# NRF52833.net
KiCad netlist of a schematic drawn in Altium Designer
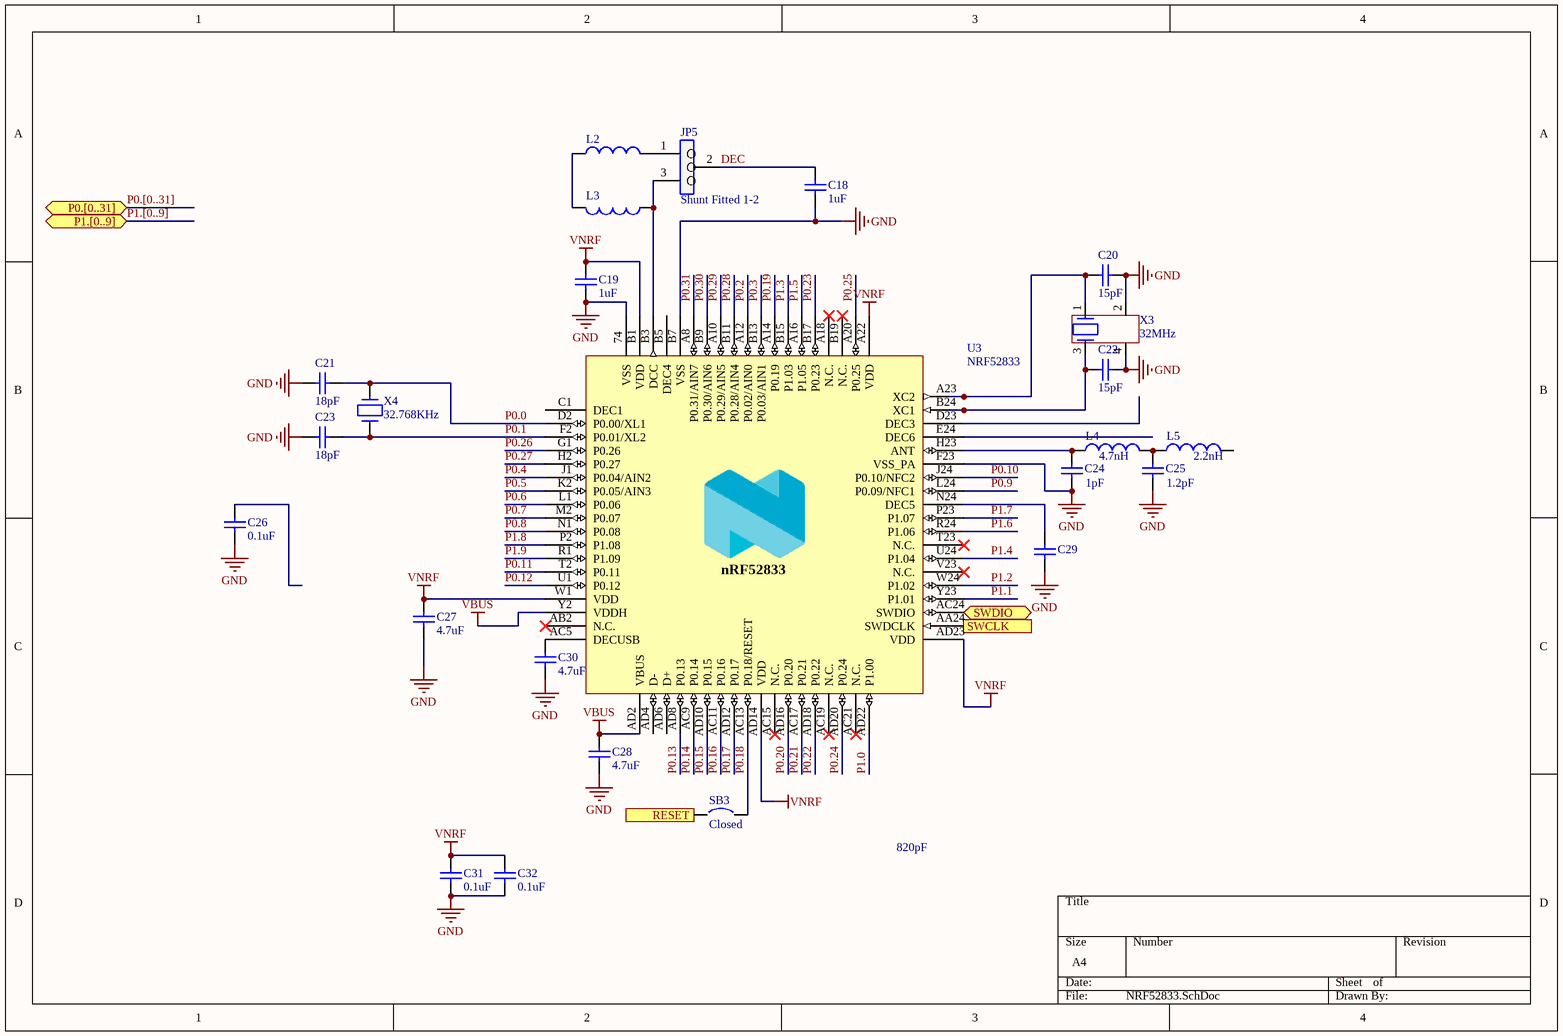
[diagram p0: NRF52833.SchDoc]

(export (version "E")
  (design (tool "Eeschema 10.0.6"))
  (components
    (comp (ref "C18")
      (value "1uF")
      (footprint "C0603[1608X92]")
      (description "1uF 6.3V 10% 0603 (1608 Metric)")
      (fields (field (name "PARTNUMBER") "GRM188R60J105KA01D") (field (name "MANUFACTURER") "Murata"))
      (libsource (lib "Capacitors") (part "CAP_1uF_6.3V_0603_10%"))
    )
    (comp (ref "C19")
      (value "1uF")
      (footprint "C0603[1608X92]")
      (description "1uF 6.3V 10% 0603 (1608 Metric)")
      (fields (field (name "PARTNUMBER") "GRM188R60J105KA01D") (field (name "MANUFACTURER") "Murata"))
      (libsource (lib "Capacitors") (part "CAP_1uF_6.3V_0603_10%"))
    )
    (comp (ref "C20")
      (value "15pF")
      (footprint "C0603[1608X92]")
      (description "15pF 50V 1% 0603 (1608 Metric)")
      (fields (field (name "PARTNUMBER") "06035A150FAT2A") (field (name "MANUFACTURER") "AVX Corporation"))
      (libsource (lib "Capacitors") (part "CAP_15pF_50V_0603_1%"))
    )
    (comp (ref "C21")
      (value "18pF")
      (footprint "C0603[1608X92]")
      (description "18pF 50V 1% 0603 (1608 Metric)")
      (fields (field (name "PARTNUMBER") "06035A180FAT2A") (field (name "MANUFACTURER") "AVX Corporation"))
      (libsource (lib "Capacitors") (part "CAP_18pF_50V_0603_1%"))
    )
    (comp (ref "C22")
      (value "15pF")
      (footprint "C0603[1608X92]")
      (description "15pF 50V 1% 0603 (1608 Metric)")
      (fields (field (name "PARTNUMBER") "06035A150FAT2A") (field (name "MANUFACTURER") "AVX Corporation"))
      (libsource (lib "Capacitors") (part "CAP_15pF_50V_0603_1%"))
    )
    (comp (ref "C23")
      (value "18pF")
      (footprint "C0603[1608X92]")
      (description "18pF 50V 1% 0603 (1608 Metric)")
      (fields (field (name "PARTNUMBER") "06035A180FAT2A") (field (name "MANUFACTURER") "AVX Corporation"))
      (libsource (lib "Capacitors") (part "CAP_18pF_50V_0603_1%"))
    )
    (comp (ref "C24")
      (value "CAPACITOR 0603")
      (footprint "C0603[1608X92]")
      (description "Empty CAPACITOR 0603 (1608 Metric)")
      (libsource (lib "Capacitors") (part "CAP 0603"))
    )
    (comp (ref "C25")
      (value "CAPACITOR 0603")
      (footprint "C0603[1608X92]")
      (description "Empty CAPACITOR 0603 (1608 Metric)")
      (libsource (lib "Capacitors") (part "CAP 0603"))
    )
    (comp (ref "C26")
      (value "0.1uF")
      (footprint "C0603[1608X92]")
      (description "0.1uF 16V 10% 0603 (1608 Metric)")
      (fields (field (name "PARTNUMBER") "GCM188R71C104KA37D") (field (name "MANUFACTURER") "Murata"))
      (libsource (lib "Capacitors") (part "CAP_0.1uF_16V_0603_10%"))
    )
    (comp (ref "C27")
      (value "4.7uF")
      (footprint "C0603[1608X92]")
      (description "4.7uF 16V 10% 0603 (1608 Metric)")
      (fields (field (name "PARTNUMBER") "GRM188R61A475KE15D") (field (name "MANUFACTURER") "Murata"))
      (libsource (lib "Capacitors") (part "CAP_4.7uF_16V_0603_10%"))
    )
    (comp (ref "C28")
      (value "4.7uF")
      (footprint "C0603[1608X92]")
      (description "4.7uF 16V 10% 0603 (1608 Metric)")
      (fields (field (name "PARTNUMBER") "GRM188R61A475KE15D") (field (name "MANUFACTURER") "Murata"))
      (libsource (lib "Capacitors") (part "CAP_4.7uF_16V_0603_10%"))
    )
    (comp (ref "C29")
      (value "CAPACITOR 0603")
      (footprint "C0603[1608X92]")
      (description "Empty CAPACITOR 0603 (1608 Metric)")
      (libsource (lib "Capacitors") (part "CAP 0603"))
    )
    (comp (ref "C30")
      (value "4.7uF")
      (footprint "C0603[1608X92]")
      (description "4.7uF 16V 10% 0603 (1608 Metric)")
      (fields (field (name "PARTNUMBER") "GRM188R61A475KE15D") (field (name "MANUFACTURER") "Murata"))
      (libsource (lib "Capacitors") (part "CAP_4.7uF_16V_0603_10%"))
    )
    (comp (ref "C31")
      (value "0.1uF")
      (footprint "C0603[1608X92]")
      (description "0.1uF 16V 10% 0603 (1608 Metric)")
      (fields (field (name "PARTNUMBER") "GCM188R71C104KA37D") (field (name "MANUFACTURER") "Murata"))
      (libsource (lib "Capacitors") (part "CAP_0.1uF_16V_0603_10%"))
    )
    (comp (ref "C32")
      (value "0.1uF")
      (footprint "C0603[1608X92]")
      (description "0.1uF 16V 10% 0603 (1608 Metric)")
      (fields (field (name "PARTNUMBER") "GCM188R71C104KA37D") (field (name "MANUFACTURER") "Murata"))
      (libsource (lib "Capacitors") (part "CAP_0.1uF_16V_0603_10%"))
    )
    (comp (ref "JP5")
      (value "Shunt Fitted 1-2")
      (footprint "HDR1X3")
      (description "Header, 3x1, 2,54mm, VR, TH, Height 5.84mm/2.54mm - Shunt Fitted 1-2 by default")
      (fields
        (field (name "INTERNAL_PART_NUMBER") "MCD-00684")
        (field (name "MANUFACTURER_PART_NUMBER") "TSW-103-07-F-S")
        (field (name "PROVIDED_BY") "SUBCO")
      )
      (libsource (lib "Connectors") (part "Jumper_Header 3x1 Fitted 1-2"))
    )
    (comp (ref "L2")
      (value "INDUCTOR 0603")
      (footprint "IND0603")
      (description "Empty INDUCTOR 0603")
      (libsource (lib "Inductors") (part "IND 0603"))
    )
    (comp (ref "L3")
      (value "INDUCTOR 0603")
      (footprint "IND0603")
      (description "Empty INDUCTOR 0603")
      (libsource (lib "Inductors") (part "IND 0603"))
    )
    (comp (ref "L4")
      (value "INDUCTOR 0603")
      (footprint "IND0603")
      (description "Empty INDUCTOR 0603")
      (libsource (lib "Inductors") (part "IND 0603"))
    )
    (comp (ref "L5")
      (value "INDUCTOR 0603")
      (footprint "IND0603")
      (description "Empty INDUCTOR 0603")
      (libsource (lib "Inductors") (part "IND 0603"))
    )
    (comp (ref "SB3")
      (value "Closed")
      (footprint "SB_0603")
      (description "Circuit Breaker")
      (fields (field (name "PUBLISHER") "Altium Limited"))
      (libsource (lib "Inductors") (part "Circuit Breaker_close"))
    )
    (comp (ref "U3")
      (value "NRF52833")
      (footprint "AQFN-73")
      (description "Multi-protocol Bluetooth Low Energy, IEEE 802.15.4, ANT and 2.4GHz proprietary system-on-chip")
      (fields
        (field (name "PARTNUMBER") "nRF52833-QIAA")
        (field (name "MANUFACTURER") "Nordic Semiconductor")
      )
      (libsource (lib "ICs") (part "NRF52833"))
    )
    (comp (ref "X3")
      (value "32MHz")
      (footprint "4-SMD")
      (description "Crystal 32MHz, 6pF, +-10ppm, 60ohms max, SMD")
      (fields (field (name "PARTNUMBER") "NX2016SA-32MHZ-EXS00A-CS07977") (field (name "MANUFACTURER") "NDK"))
      (libsource (lib "Oscillators") (part "NX2016SA 32MHz"))
    )
    (comp (ref "X4")
      (value "32.768KHz")
      (footprint "2-SMD")
      (description "Crystal 32.768kHz, 6pF, +-20ppm, 50Kohms max, SMD")
      (fields
        (field (name "PARTNUMBER") "NX3215SA-32.768KHz-EXS00A-MU00525")
        (field (name "MANUFACTURER") "NDK")
      )
      (libsource (lib "Oscillators") (part "NX3215SA 32.768KHz"))
    )
  )
  (nets
    (net (code "1") (name "/DEC") (class "Default")
      (node (ref "C18") (pin "2") (pinfunction "2_2") (pintype "passive"))
      (node (ref "JP5") (pin "2") (pinfunction "2_2") (pintype "passive"))
    )
    (net (code "2") (name "/P0.0") (class "Default")
      (node (ref "C21") (pin "1") (pinfunction "1_1") (pintype "passive"))
      (node (ref "U3") (pin "D2") (pinfunction "P0.00/XL1_D2") (pintype "bidirectional"))
      (node (ref "X4") (pin "2") (pinfunction "X2_2") (pintype "passive"))
    )
    (net (code "3") (name "/P0.1") (class "Default")
      (node (ref "C23") (pin "1") (pinfunction "1_1") (pintype "passive"))
      (node (ref "U3") (pin "F2") (pinfunction "P0.01/XL2_F2") (pintype "bidirectional"))
      (node (ref "X4") (pin "1") (pinfunction "X1_1") (pintype "passive"))
    )
    (net (code "4") (name "/P0.2") (class "Default")
      (node (ref "U3") (pin "A12") (pinfunction "P0.02/AIN0_A12") (pintype "bidirectional"))
    )
    (net (code "5") (name "/P0.3") (class "Default")
      (node (ref "U3") (pin "B13") (pinfunction "P0.03/AIN1_B13") (pintype "bidirectional"))
    )
    (net (code "6") (name "/P0.4") (class "Default")
      (node (ref "U3") (pin "J1") (pinfunction "P0.04/AIN2_J1") (pintype "bidirectional"))
    )
    (net (code "7") (name "/P0.5") (class "Default")
      (node (ref "U3") (pin "K2") (pinfunction "P0.05/AIN3_K2") (pintype "bidirectional"))
    )
    (net (code "8") (name "/P0.6") (class "Default")
      (node (ref "U3") (pin "L1") (pinfunction "P0.06_L1") (pintype "bidirectional"))
    )
    (net (code "9") (name "/P0.7") (class "Default")
      (node (ref "U3") (pin "M2") (pinfunction "P0.07_M2") (pintype "bidirectional"))
    )
    (net (code "10") (name "/P0.8") (class "Default")
      (node (ref "U3") (pin "N1") (pinfunction "P0.08_N1") (pintype "bidirectional"))
    )
    (net (code "11") (name "/P0.9") (class "Default")
      (node (ref "U3") (pin "L24") (pinfunction "P0.09/NFC1_L24") (pintype "bidirectional"))
    )
    (net (code "12") (name "/P0.10") (class "Default")
      (node (ref "U3") (pin "J24") (pinfunction "P0.10/NFC2_J24") (pintype "bidirectional"))
    )
    (net (code "13") (name "/P0.11") (class "Default")
      (node (ref "U3") (pin "T2") (pinfunction "P0.11_T2") (pintype "bidirectional"))
    )
    (net (code "14") (name "/P0.12") (class "Default")
      (node (ref "U3") (pin "U1") (pinfunction "P0.12_U1") (pintype "bidirectional"))
    )
    (net (code "15") (name "/P0.13") (class "Default")
      (node (ref "U3") (pin "AD8") (pinfunction "P0.13_AD8") (pintype "bidirectional"))
    )
    (net (code "16") (name "/P0.14") (class "Default")
      (node (ref "U3") (pin "AC9") (pinfunction "P0.14_AC9") (pintype "bidirectional"))
    )
    (net (code "17") (name "/P0.15") (class "Default")
      (node (ref "U3") (pin "AD10") (pinfunction "P0.15_AD10") (pintype "bidirectional"))
    )
    (net (code "18") (name "/P0.16") (class "Default")
      (node (ref "U3") (pin "AC11") (pinfunction "P0.16_AC11") (pintype "bidirectional"))
    )
    (net (code "19") (name "/P0.17") (class "Default")
      (node (ref "U3") (pin "AD12") (pinfunction "P0.17_AD12") (pintype "bidirectional"))
    )
    (net (code "20") (name "/P0.18") (class "Default")
      (node (ref "SB3") (pin "2") (pinfunction "2_2") (pintype "passive"))
      (node (ref "U3") (pin "AC13") (pinfunction "P0.18/RESET_AC13") (pintype "bidirectional"))
    )
    (net (code "21") (name "/P0.19") (class "Default")
      (node (ref "U3") (pin "A14") (pinfunction "P0.19_A14") (pintype "bidirectional"))
    )
    (net (code "22") (name "/P0.20") (class "Default")
      (node (ref "U3") (pin "AD16") (pinfunction "P0.20_AD16") (pintype "bidirectional"))
    )
    (net (code "23") (name "/P0.21") (class "Default")
      (node (ref "U3") (pin "AC17") (pinfunction "P0.21_AC17") (pintype "bidirectional"))
    )
    (net (code "24") (name "/P0.22") (class "Default")
      (node (ref "U3") (pin "AD18") (pinfunction "P0.22_AD18") (pintype "bidirectional"))
    )
    (net (code "25") (name "/P0.23") (class "Default")
      (node (ref "U3") (pin "B17") (pinfunction "P0.23_B17") (pintype "bidirectional"))
    )
    (net (code "26") (name "/P0.24") (class "Default")
      (node (ref "U3") (pin "AD20") (pinfunction "P0.24_AD20") (pintype "bidirectional"))
    )
    (net (code "27") (name "/P0.25") (class "Default")
      (node (ref "U3") (pin "A20") (pinfunction "P0.25_A20") (pintype "bidirectional"))
    )
    (net (code "28") (name "/P0.26") (class "Default")
      (node (ref "U3") (pin "G1") (pinfunction "P0.26_G1") (pintype "bidirectional"))
    )
    (net (code "29") (name "/P0.27") (class "Default")
      (node (ref "U3") (pin "H2") (pinfunction "P0.27_H2") (pintype "bidirectional"))
    )
    (net (code "30") (name "/P0.28") (class "Default")
      (node (ref "U3") (pin "B11") (pinfunction "P0.28/AIN4_B11") (pintype "bidirectional"))
    )
    (net (code "31") (name "/P0.29") (class "Default")
      (node (ref "U3") (pin "A10") (pinfunction "P0.29/AIN5_A10") (pintype "bidirectional"))
    )
    (net (code "32") (name "/P0.30") (class "Default")
      (node (ref "U3") (pin "B9") (pinfunction "P0.30/AIN6_B9") (pintype "bidirectional"))
    )
    (net (code "33") (name "/P0.31") (class "Default")
      (node (ref "U3") (pin "A8") (pinfunction "P0.31/AIN7_A8") (pintype "bidirectional"))
    )
    (net (code "35") (name "/P1.0") (class "Default")
      (node (ref "U3") (pin "AD22") (pinfunction "P1.00_AD22") (pintype "bidirectional"))
    )
    (net (code "36") (name "/P1.1") (class "Default")
      (node (ref "U3") (pin "Y23") (pinfunction "P1.01_Y23") (pintype "bidirectional"))
    )
    (net (code "37") (name "/P1.2") (class "Default")
      (node (ref "U3") (pin "W24") (pinfunction "P1.02_W24") (pintype "bidirectional"))
    )
    (net (code "38") (name "/P1.3") (class "Default")
      (node (ref "U3") (pin "B15") (pinfunction "P1.03_B15") (pintype "bidirectional"))
    )
    (net (code "39") (name "/P1.4") (class "Default")
      (node (ref "U3") (pin "U24") (pinfunction "P1.04_U24") (pintype "bidirectional"))
    )
    (net (code "40") (name "/P1.5") (class "Default")
      (node (ref "U3") (pin "A16") (pinfunction "P1.05_A16") (pintype "bidirectional"))
    )
    (net (code "41") (name "/P1.6") (class "Default")
      (node (ref "U3") (pin "R24") (pinfunction "P1.06_R24") (pintype "bidirectional"))
    )
    (net (code "42") (name "/P1.7") (class "Default")
      (node (ref "U3") (pin "P23") (pinfunction "P1.07_P23") (pintype "bidirectional"))
    )
    (net (code "43") (name "/P1.8") (class "Default")
      (node (ref "U3") (pin "P2") (pinfunction "P1.08_P2") (pintype "bidirectional"))
    )
    (net (code "44") (name "/P1.9") (class "Default")
      (node (ref "U3") (pin "R1") (pinfunction "P1.09_R1") (pintype "bidirectional"))
    )
    (net (code "46") (name "/RESET") (class "Default")
      (node (ref "SB3") (pin "1") (pinfunction "1_1") (pintype "passive"))
    )
    (net (code "47") (name "/SWCLK") (class "Default")
      (node (ref "U3") (pin "AA24") (pinfunction "SWDCLK_AA24") (pintype "input"))
    )
    (net (code "48") (name "/SWDIO") (class "Default")
      (node (ref "U3") (pin "AC24") (pinfunction "SWDIO_AC24") (pintype "bidirectional"))
    )
    (net (code "49") (name "GND") (class "Default")
      (node (ref "C18") (pin "1") (pinfunction "1_1") (pintype "passive"))
      (node (ref "C19") (pin "1") (pinfunction "1_1") (pintype "passive"))
      (node (ref "C20") (pin "1") (pinfunction "1_1") (pintype "passive"))
      (node (ref "C21") (pin "2") (pinfunction "2_2") (pintype "passive"))
      (node (ref "C22") (pin "1") (pinfunction "1_1") (pintype "passive"))
      (node (ref "C23") (pin "2") (pinfunction "2_2") (pintype "passive"))
      (node (ref "C24") (pin "1") (pinfunction "1_1") (pintype "passive"))
      (node (ref "C25") (pin "1") (pinfunction "1_1") (pintype "passive"))
      (node (ref "C26") (pin "2") (pinfunction "2_2") (pintype "passive"))
      (node (ref "C27") (pin "1") (pinfunction "1_1") (pintype "passive"))
      (node (ref "C28") (pin "1") (pinfunction "1_1") (pintype "passive"))
      (node (ref "C29") (pin "1") (pinfunction "1_1") (pintype "passive"))
      (node (ref "C30") (pin "1") (pinfunction "1_1") (pintype "passive"))
      (node (ref "C31") (pin "2") (pinfunction "2_2") (pintype "passive"))
      (node (ref "C32") (pin "2") (pinfunction "2_2") (pintype "passive"))
      (node (ref "U3") (pin "74") (pinfunction "VSS_74") (pintype "power_in"))
      (node (ref "U3") (pin "B7") (pinfunction "VSS_B7") (pintype "power_in"))
      (node (ref "U3") (pin "F23") (pinfunction "VSS_PA_F23") (pintype "power_in"))
      (node (ref "X3") (pin "2") (pinfunction "2_2") (pintype "passive"))
      (node (ref "X3") (pin "4") (pinfunction "4_4") (pintype "passive"))
    )
    (net (code "50") (name "Net-(C25-Pad2)") (class "Default")
      (node (ref "C25") (pin "2") (pinfunction "2_2") (pintype "passive"))
      (node (ref "L4") (pin "2") (pinfunction "2_2") (pintype "passive"))
      (node (ref "L5") (pin "1") (pinfunction "1_1") (pintype "passive"))
    )
    (net (code "51") (name "Net-(JP5-Pad1)") (class "Default")
      (node (ref "JP5") (pin "1") (pinfunction "1_1") (pintype "passive"))
      (node (ref "L2") (pin "2") (pinfunction "2_2") (pintype "passive"))
    )
    (net (code "52") (name "Net-(L2-Pad1)") (class "Default")
      (node (ref "L2") (pin "1") (pinfunction "1_1") (pintype "passive"))
      (node (ref "L3") (pin "2") (pinfunction "2_2") (pintype "passive"))
    )
    (net (code "53") (name "Net-(U3-ANT)") (class "Default")
      (node (ref "C24") (pin "2") (pinfunction "2_2") (pintype "passive"))
      (node (ref "L4") (pin "1") (pinfunction "1_1") (pintype "passive"))
      (node (ref "U3") (pin "H23") (pinfunction "ANT_H23") (pintype "bidirectional"))
    )
    (net (code "54") (name "Net-(U3-DCC)") (class "Default")
      (node (ref "JP5") (pin "3") (pinfunction "3_3") (pintype "passive"))
      (node (ref "L3") (pin "1") (pinfunction "1_1") (pintype "passive"))
      (node (ref "U3") (pin "B3") (pinfunction "DCC_B3") (pintype "output"))
    )
    (net (code "55") (name "Net-(U3-DEC5)") (class "Default")
      (node (ref "C29") (pin "2") (pinfunction "2_2") (pintype "passive"))
      (node (ref "U3") (pin "N24") (pinfunction "DEC5_N24") (pintype "power_in"))
    )
    (net (code "56") (name "Net-(U3-DECUSB)") (class "Default")
      (node (ref "C30") (pin "2") (pinfunction "2_2") (pintype "passive"))
      (node (ref "U3") (pin "AC5") (pinfunction "DECUSB_AC5") (pintype "power_in"))
    )
    (net (code "57") (name "Net-(U3-XC1)") (class "Default")
      (node (ref "C22") (pin "2") (pinfunction "2_2") (pintype "passive"))
      (node (ref "U3") (pin "B24") (pinfunction "XC1_B24") (pintype "input"))
      (node (ref "X3") (pin "3") (pinfunction "3_3") (pintype "passive"))
    )
    (net (code "58") (name "Net-(U3-XC2)") (class "Default")
      (node (ref "C20") (pin "2") (pinfunction "2_2") (pintype "passive"))
      (node (ref "U3") (pin "A23") (pinfunction "XC2_A23") (pintype "output"))
      (node (ref "X3") (pin "1") (pinfunction "1_1") (pintype "passive"))
    )
    (net (code "59") (name "VBUS") (class "Default")
      (node (ref "C28") (pin "2") (pinfunction "2_2") (pintype "passive"))
      (node (ref "U3") (pin "AD2") (pinfunction "VBUS_AD2") (pintype "power_in"))
      (node (ref "U3") (pin "Y2") (pinfunction "VDDH_Y2") (pintype "power_in"))
    )
    (net (code "60") (name "VNRF") (class "Default")
      (node (ref "C19") (pin "2") (pinfunction "2_2") (pintype "passive"))
      (node (ref "C27") (pin "2") (pinfunction "2_2") (pintype "passive"))
      (node (ref "C31") (pin "1") (pinfunction "1_1") (pintype "passive"))
      (node (ref "C32") (pin "1") (pinfunction "1_1") (pintype "passive"))
      (node (ref "U3") (pin "A22") (pinfunction "VDD_A22") (pintype "power_in"))
      (node (ref "U3") (pin "AD14") (pinfunction "VDD_AD14") (pintype "power_in"))
      (node (ref "U3") (pin "AD23") (pinfunction "VDD_AD23") (pintype "power_in"))
      (node (ref "U3") (pin "B1") (pinfunction "VDD_B1") (pintype "power_in"))
      (node (ref "U3") (pin "W1") (pinfunction "VDD_W1") (pintype "power_in"))
    )
    (net (code "61") (name "unconnected-(C26-Pad1)") (class "Default")
      (node (ref "C26") (pin "1") (pinfunction "1_1") (pintype "passive"))
    )
    (net (code "62") (name "unconnected-(L5-Pad2)") (class "Default")
      (node (ref "L5") (pin "2") (pinfunction "2_2") (pintype "passive"))
    )
    (net (code "63") (name "unconnected-(U3-D+-PadAD6)") (class "Default")
      (node (ref "U3") (pin "AD6") (pinfunction "D+_AD6") (pintype "bidirectional"))
    )
    (net (code "64") (name "unconnected-(U3-D--PadAD4)") (class "Default")
      (node (ref "U3") (pin "AD4") (pinfunction "D-_AD4") (pintype "bidirectional"))
    )
    (net (code "65") (name "unconnected-(U3-DEC1-PadC1)") (class "Default")
      (node (ref "U3") (pin "C1") (pinfunction "DEC1_C1") (pintype "power_in"))
    )
    (net (code "66") (name "unconnected-(U3-DEC3-PadD23)") (class "Default")
      (node (ref "U3") (pin "D23") (pinfunction "DEC3_D23") (pintype "power_in"))
    )
    (net (code "67") (name "unconnected-(U3-DEC4-PadB5)") (class "Default")
      (node (ref "U3") (pin "B5") (pinfunction "DEC4_B5") (pintype "power_in"))
    )
    (net (code "68") (name "unconnected-(U3-DEC6-PadE24)") (class "Default")
      (node (ref "U3") (pin "E24") (pinfunction "DEC6_E24") (pintype "power_in"))
    )
    (net (code "69") (name "unconnected-(U3-N.C.-PadA18)") (class "Default")
      (node (ref "U3") (pin "A18") (pinfunction "N.C._A18") (pintype "passive+no_connect"))
    )
    (net (code "70") (name "unconnected-(U3-N.C.-PadAB2)") (class "Default")
      (node (ref "U3") (pin "AB2") (pinfunction "N.C._AB2") (pintype "passive+no_connect"))
    )
    (net (code "71") (name "unconnected-(U3-N.C.-PadAC15)") (class "Default")
      (node (ref "U3") (pin "AC15") (pinfunction "N.C._AC15") (pintype "passive+no_connect"))
    )
    (net (code "72") (name "unconnected-(U3-N.C.-PadAC19)") (class "Default")
      (node (ref "U3") (pin "AC19") (pinfunction "N.C._AC19") (pintype "passive+no_connect"))
    )
    (net (code "73") (name "unconnected-(U3-N.C.-PadAC21)") (class "Default")
      (node (ref "U3") (pin "AC21") (pinfunction "N.C._AC21") (pintype "passive+no_connect"))
    )
    (net (code "74") (name "unconnected-(U3-N.C.-PadB19)") (class "Default")
      (node (ref "U3") (pin "B19") (pinfunction "N.C._B19") (pintype "passive+no_connect"))
    )
    (net (code "75") (name "unconnected-(U3-N.C.-PadT23)") (class "Default")
      (node (ref "U3") (pin "T23") (pinfunction "N.C._T23") (pintype "passive+no_connect"))
    )
    (net (code "76") (name "unconnected-(U3-N.C.-PadV23)") (class "Default")
      (node (ref "U3") (pin "V23") (pinfunction "N.C._V23") (pintype "passive+no_connect"))
    )
  )
)
